# Power.net
KiCad netlist of a schematic drawn in Altium Designer
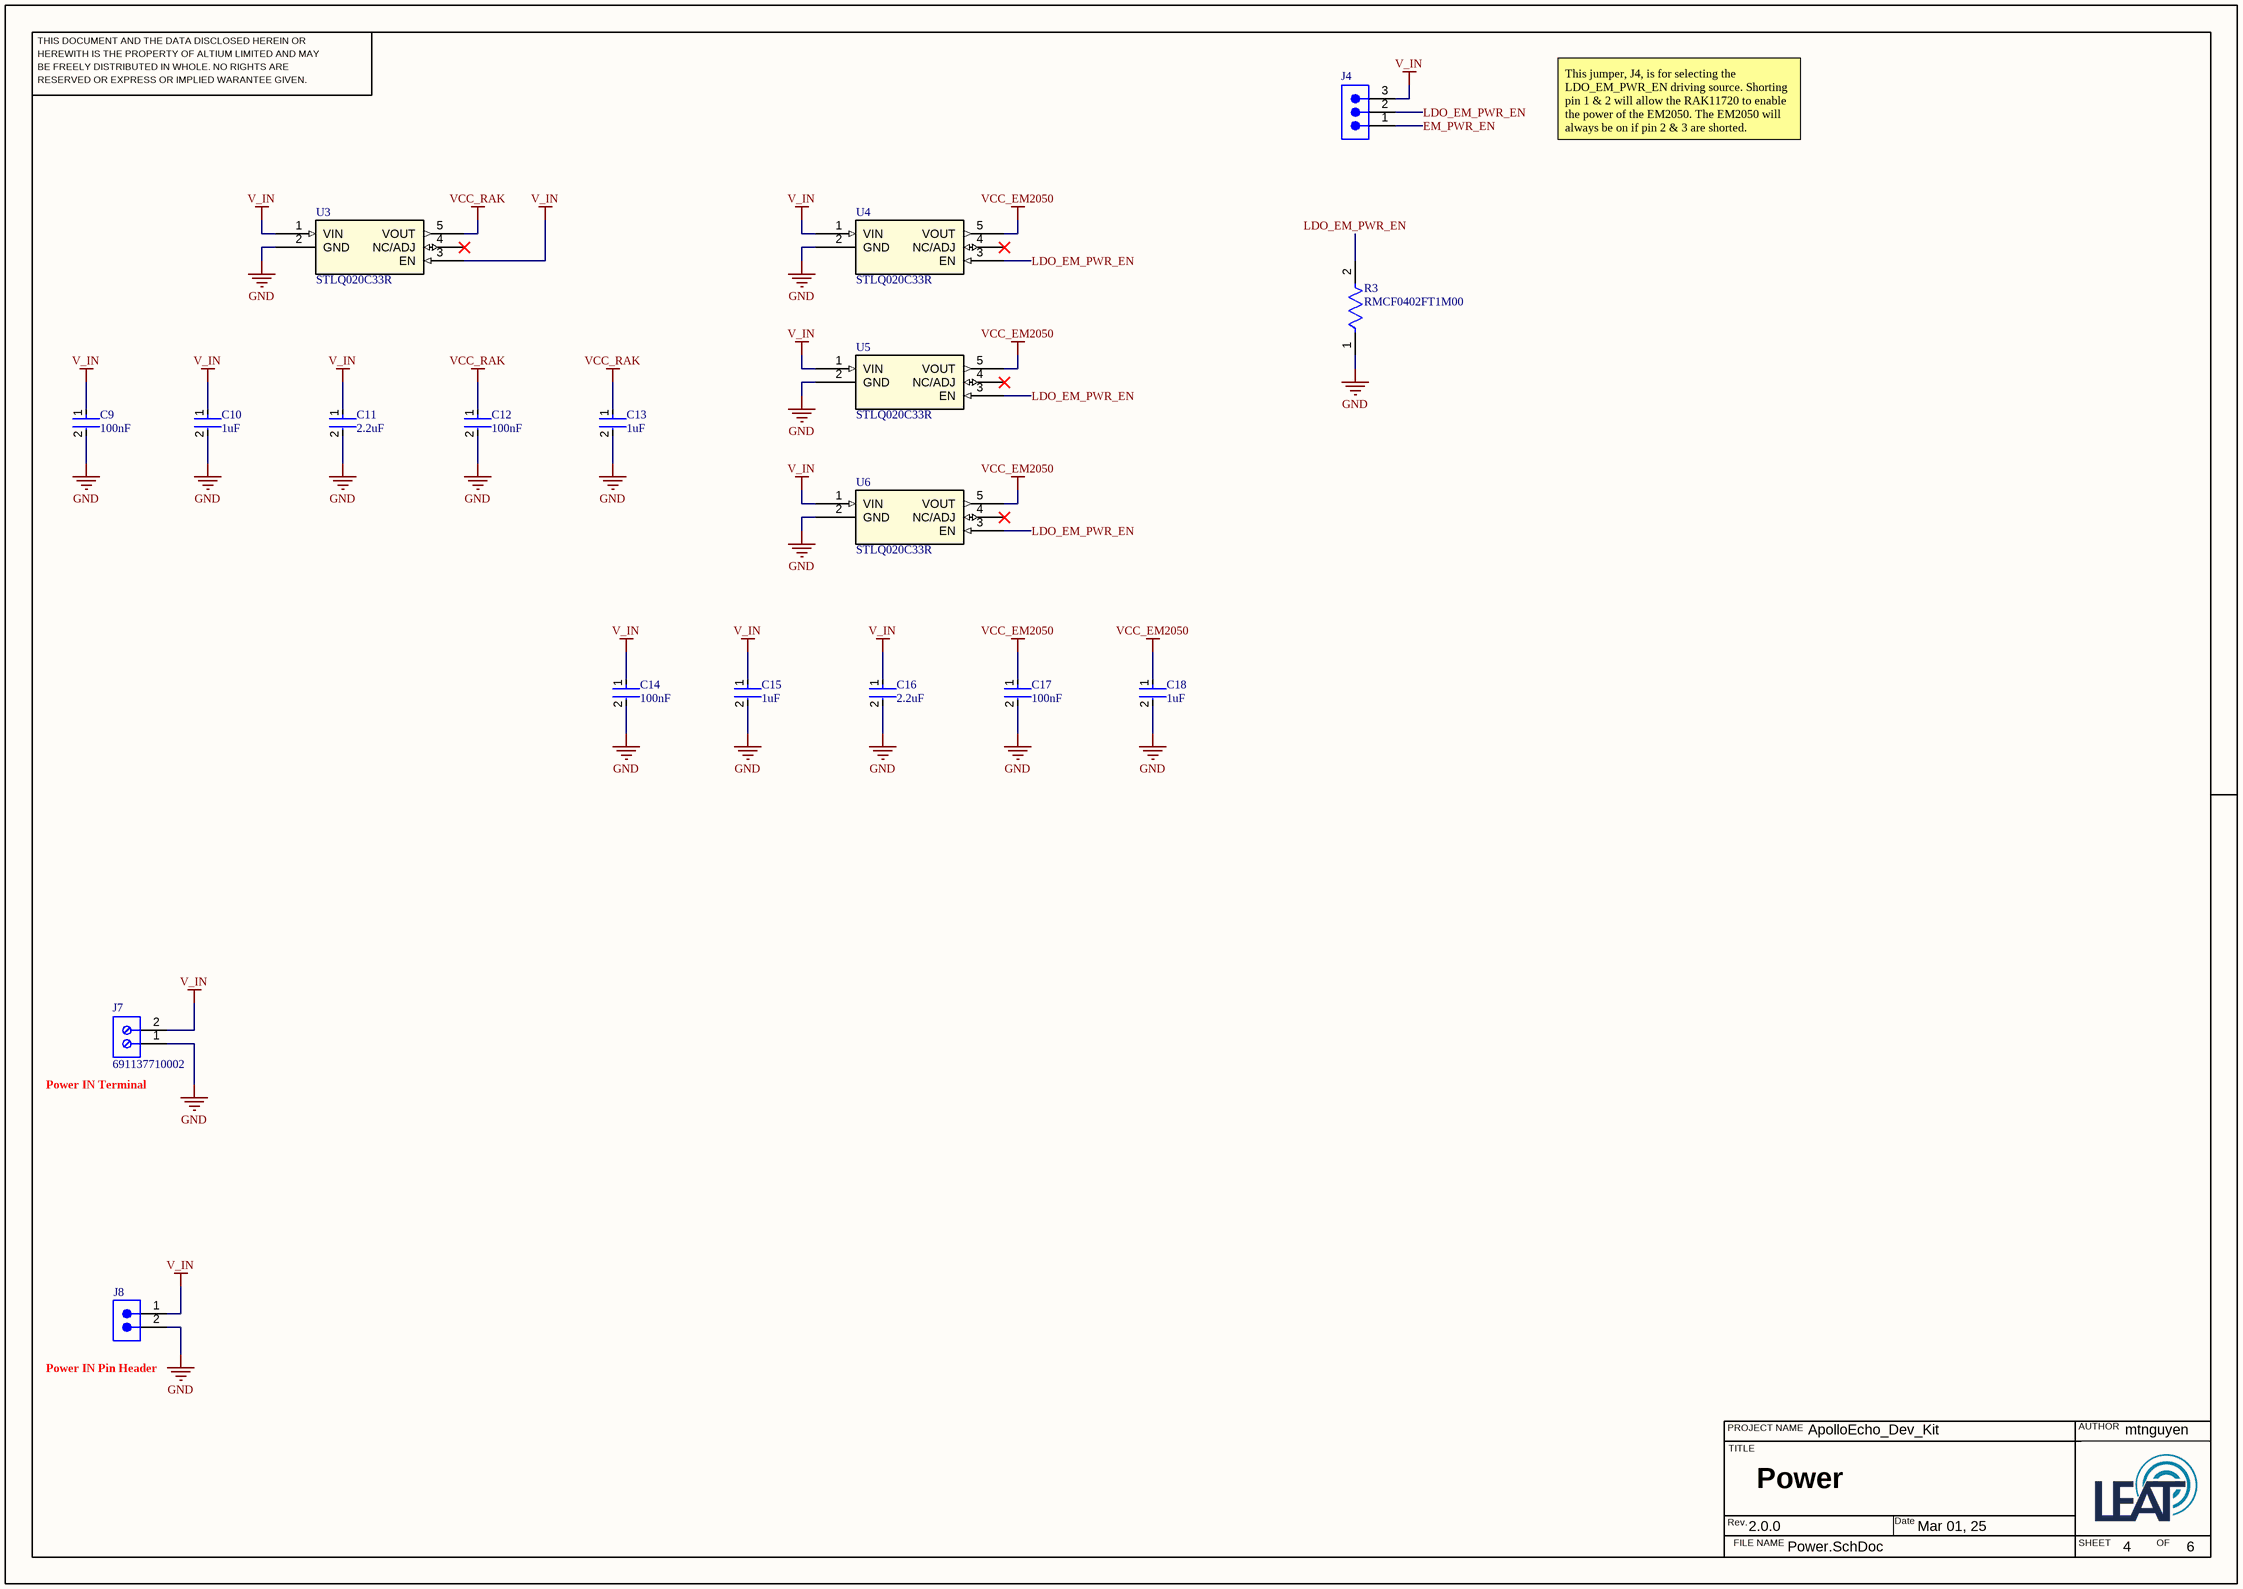
[diagram p0: Power.SchDoc]

(export (version "E")
  (design (tool "Eeschema 10.0.6"))
  (components
    (comp (ref "C9")
      (value "0402ZD104KAT2A")
      (footprint "FP-0402-L_1_0_1-W_0_5_0_1-IPC_C")
      (description "General Purpose Ceramic Capacitor, 0402, 100nF, 10%, X5R, 15%, 10V")
      (fields
        (field (name "VOLTAGE") "10V")
        (field (name "TOLERANCE") "10%")
        (field (name "CAPACITANCE") "100nF")
      )
      (libsource (lib "ApolloEcho_Dev_Kit") (part "b4654b650e69147ec39a6b967a45e02"))
    )
    (comp (ref "C10")
      (value "EMK105BJ105KV-F")
      (footprint "FP-0402-L_1_0_0_05-W_0_5-IPC_A")
      (description "None")
      (fields (field (name "TOLERANCE") "10%") (field (name "CAPACITANCE") "1uF"))
      (libsource (lib "ApolloEcho_Dev_Kit") (part "b4654b650e69147ec39a6b967a45e02"))
    )
    (comp (ref "C11")
      (value "C1005X5R1A225K050BC")
      (footprint "FP-C1005-050-0_05-IPC_A")
      (description "Multilayer Ceramic Capacitors 2.2μF ±10% 10V X5R SMD 0402")
      (fields
        (field (name "TOLERANCE") "10%")
        (field (name "VOLTAGE") "10V")
        (field (name "CAPACITANCE") "2.2uF")
      )
      (libsource (lib "ApolloEcho_Dev_Kit") (part "b4654b650e69147ec39a6b967a45e02"))
    )
    (comp (ref "C12")
      (value "0402ZD104KAT2A")
      (footprint "FP-0402-L_1_0_1-W_0_5_0_1-IPC_C")
      (description "General Purpose Ceramic Capacitor, 0402, 100nF, 10%, X5R, 15%, 10V")
      (fields
        (field (name "VOLTAGE") "10V")
        (field (name "TOLERANCE") "10%")
        (field (name "CAPACITANCE") "100nF")
      )
      (libsource (lib "ApolloEcho_Dev_Kit") (part "b4654b650e69147ec39a6b967a45e02"))
    )
    (comp (ref "C13")
      (value "EMK105BJ105KV-F")
      (footprint "FP-0402-L_1_0_0_05-W_0_5-IPC_A")
      (description "None")
      (fields (field (name "TOLERANCE") "10%") (field (name "CAPACITANCE") "1uF"))
      (libsource (lib "ApolloEcho_Dev_Kit") (part "b4654b650e69147ec39a6b967a45e02"))
    )
    (comp (ref "C14")
      (value "0402ZD104KAT2A")
      (footprint "FP-0402-L_1_0_1-W_0_5_0_1-IPC_C")
      (description "General Purpose Ceramic Capacitor, 0402, 100nF, 10%, X5R, 15%, 10V")
      (fields
        (field (name "VOLTAGE") "10V")
        (field (name "TOLERANCE") "10%")
        (field (name "CAPACITANCE") "100nF")
      )
      (libsource (lib "ApolloEcho_Dev_Kit") (part "b4654b650e69147ec39a6b967a45e02"))
    )
    (comp (ref "C15")
      (value "EMK105BJ105KV-F")
      (footprint "FP-0402-L_1_0_0_05-W_0_5-IPC_A")
      (description "None")
      (fields (field (name "TOLERANCE") "10%") (field (name "CAPACITANCE") "1uF"))
      (libsource (lib "ApolloEcho_Dev_Kit") (part "b4654b650e69147ec39a6b967a45e02"))
    )
    (comp (ref "C16")
      (value "C1005X5R1A225K050BC")
      (footprint "FP-C1005-050-0_05-IPC_A")
      (description "Multilayer Ceramic Capacitors 2.2μF ±10% 10V X5R SMD 0402")
      (fields
        (field (name "TOLERANCE") "10%")
        (field (name "VOLTAGE") "10V")
        (field (name "CAPACITANCE") "2.2uF")
      )
      (libsource (lib "ApolloEcho_Dev_Kit") (part "b4654b650e69147ec39a6b967a45e02"))
    )
    (comp (ref "C17")
      (value "0402ZD104KAT2A")
      (footprint "FP-0402-L_1_0_1-W_0_5_0_1-IPC_C")
      (description "General Purpose Ceramic Capacitor, 0402, 100nF, 10%, X5R, 15%, 10V")
      (fields
        (field (name "VOLTAGE") "10V")
        (field (name "TOLERANCE") "10%")
        (field (name "CAPACITANCE") "100nF")
      )
      (libsource (lib "ApolloEcho_Dev_Kit") (part "b4654b650e69147ec39a6b967a45e02"))
    )
    (comp (ref "C18")
      (value "EMK105BJ105KV-F")
      (footprint "FP-0402-L_1_0_0_05-W_0_5-IPC_A")
      (description "None")
      (fields (field (name "TOLERANCE") "10%") (field (name "CAPACITANCE") "1uF"))
      (libsource (lib "ApolloEcho_Dev_Kit") (part "b4654b650e69147ec39a6b967a45e02"))
    )
    (comp (ref "J4")
      (value "61300311121")
      (footprint "61300311121")
      (libsource (lib "ApolloEcho_Dev_Kit") (part "Header_Male_1R_03P"))
    )
    (comp (ref "J7")
      (value "691137710002")
      (footprint "691137710002")
      (libsource (lib "ApolloEcho_Dev_Kit") (part "TBL - 1R - 02P - Screw"))
    )
    (comp (ref "J8")
      (value "61300211121")
      (footprint "61300211121")
      (libsource (lib "ApolloEcho_Dev_Kit") (part "Header_Male_1R_02P"))
    )
    (comp (ref "R3")
      (value "RMCF0402FT1M00")
      (footprint "FP-RMCF0402-MFG")
      (description "1MΩ ±1% 0.063W 0402 Thick Film Chip Resistor AEC-Q200 compliant")
      (fields (field (name "TOLERANCE") "1%"))
      (libsource (lib "ApolloEcho_Dev_Kit") (part "1029c3af85768c4190bb7ad29bc67b5"))
    )
    (comp (ref "U3")
      (value "STLQ020C33R")
      (footprint "SOT323-5L_STM")
      (description "No Description Available")
      (fields (field (name "COPYRIGHT") "Copyright (C) 2023 Ultra Librarian. All rights reserved."))
      (libsource (lib "ApolloEcho_Dev_Kit") (part "STLQ020C33R"))
    )
    (comp (ref "U4")
      (value "STLQ020C33R")
      (footprint "SOT323-5L_STM")
      (description "No Description Available")
      (fields (field (name "COPYRIGHT") "Copyright (C) 2023 Ultra Librarian. All rights reserved."))
      (libsource (lib "ApolloEcho_Dev_Kit") (part "STLQ020C33R"))
    )
    (comp (ref "U5")
      (value "STLQ020C33R")
      (footprint "SOT323-5L_STM")
      (description "No Description Available")
      (fields (field (name "COPYRIGHT") "Copyright (C) 2023 Ultra Librarian. All rights reserved."))
      (libsource (lib "ApolloEcho_Dev_Kit") (part "STLQ020C33R"))
    )
    (comp (ref "U6")
      (value "STLQ020C33R")
      (footprint "SOT323-5L_STM")
      (description "No Description Available")
      (fields (field (name "COPYRIGHT") "Copyright (C) 2023 Ultra Librarian. All rights reserved."))
      (libsource (lib "ApolloEcho_Dev_Kit") (part "STLQ020C33R"))
    )
  )
  (nets
    (net (code "1") (name "/EM_PWR_EN") (class "Default")
      (node (ref "J4") (pin "1") (pinfunction "1_1") (pintype "passive"))
    )
    (net (code "2") (name "/LDO_EM_PWR_EN") (class "Default")
      (node (ref "J4") (pin "2") (pinfunction "2_2") (pintype "passive"))
      (node (ref "R3") (pin "2") (pinfunction "2_2") (pintype "passive"))
      (node (ref "U4") (pin "3") (pinfunction "EN_3") (pintype "input"))
      (node (ref "U5") (pin "3") (pinfunction "EN_3") (pintype "input"))
      (node (ref "U6") (pin "3") (pinfunction "EN_3") (pintype "input"))
    )
    (net (code "3") (name "GND") (class "Default")
      (node (ref "C10") (pin "2") (pinfunction "2_2") (pintype "passive"))
      (node (ref "C11") (pin "2") (pinfunction "2_2") (pintype "passive"))
      (node (ref "C12") (pin "2") (pinfunction "2_2") (pintype "passive"))
      (node (ref "C13") (pin "2") (pinfunction "2_2") (pintype "passive"))
      (node (ref "C14") (pin "2") (pinfunction "2_2") (pintype "passive"))
      (node (ref "C15") (pin "2") (pinfunction "2_2") (pintype "passive"))
      (node (ref "C16") (pin "2") (pinfunction "2_2") (pintype "passive"))
      (node (ref "C17") (pin "2") (pinfunction "2_2") (pintype "passive"))
      (node (ref "C18") (pin "2") (pinfunction "2_2") (pintype "passive"))
      (node (ref "C9") (pin "2") (pinfunction "2_2") (pintype "passive"))
      (node (ref "J7") (pin "1") (pinfunction "1_1") (pintype "passive"))
      (node (ref "J8") (pin "2") (pinfunction "2_2") (pintype "passive"))
      (node (ref "R3") (pin "1") (pinfunction "1_1") (pintype "passive"))
      (node (ref "U3") (pin "2") (pinfunction "GND_2") (pintype "power_in"))
      (node (ref "U4") (pin "2") (pinfunction "GND_2") (pintype "power_in"))
      (node (ref "U5") (pin "2") (pinfunction "GND_2") (pintype "power_in"))
      (node (ref "U6") (pin "2") (pinfunction "GND_2") (pintype "power_in"))
    )
    (net (code "4") (name "VCC_EM2050") (class "Default")
      (node (ref "C17") (pin "1") (pinfunction "1_1") (pintype "passive"))
      (node (ref "C18") (pin "1") (pinfunction "1_1") (pintype "passive"))
      (node (ref "U4") (pin "5") (pinfunction "VOUT_5") (pintype "output"))
      (node (ref "U5") (pin "5") (pinfunction "VOUT_5") (pintype "output"))
      (node (ref "U6") (pin "5") (pinfunction "VOUT_5") (pintype "output"))
    )
    (net (code "5") (name "VCC_RAK") (class "Default")
      (node (ref "C12") (pin "1") (pinfunction "1_1") (pintype "passive"))
      (node (ref "C13") (pin "1") (pinfunction "1_1") (pintype "passive"))
      (node (ref "U3") (pin "5") (pinfunction "VOUT_5") (pintype "output"))
    )
    (net (code "6") (name "V_IN") (class "Default")
      (node (ref "C10") (pin "1") (pinfunction "1_1") (pintype "passive"))
      (node (ref "C11") (pin "1") (pinfunction "1_1") (pintype "passive"))
      (node (ref "C14") (pin "1") (pinfunction "1_1") (pintype "passive"))
      (node (ref "C15") (pin "1") (pinfunction "1_1") (pintype "passive"))
      (node (ref "C16") (pin "1") (pinfunction "1_1") (pintype "passive"))
      (node (ref "C9") (pin "1") (pinfunction "1_1") (pintype "passive"))
      (node (ref "J4") (pin "3") (pinfunction "3_3") (pintype "passive"))
      (node (ref "J7") (pin "2") (pinfunction "2_2") (pintype "passive"))
      (node (ref "J8") (pin "1") (pinfunction "1_1") (pintype "passive"))
      (node (ref "U3") (pin "1") (pinfunction "VIN_1") (pintype "input"))
      (node (ref "U3") (pin "3") (pinfunction "EN_3") (pintype "input"))
      (node (ref "U4") (pin "1") (pinfunction "VIN_1") (pintype "input"))
      (node (ref "U5") (pin "1") (pinfunction "VIN_1") (pintype "input"))
      (node (ref "U6") (pin "1") (pinfunction "VIN_1") (pintype "input"))
    )
    (net (code "7") (name "unconnected-(U3-NC{slash}ADJ-Pad4)") (class "Default")
      (node (ref "U3") (pin "4") (pinfunction "NC/ADJ_4") (pintype "bidirectional+no_connect"))
    )
    (net (code "8") (name "unconnected-(U4-NC{slash}ADJ-Pad4)") (class "Default")
      (node (ref "U4") (pin "4") (pinfunction "NC/ADJ_4") (pintype "bidirectional+no_connect"))
    )
    (net (code "9") (name "unconnected-(U5-NC{slash}ADJ-Pad4)") (class "Default")
      (node (ref "U5") (pin "4") (pinfunction "NC/ADJ_4") (pintype "bidirectional+no_connect"))
    )
    (net (code "10") (name "unconnected-(U6-NC{slash}ADJ-Pad4)") (class "Default")
      (node (ref "U6") (pin "4") (pinfunction "NC/ADJ_4") (pintype "bidirectional+no_connect"))
    )
  )
)
